# I2C_Switch.net
KiCad netlist of a schematic drawn in Altium Designer
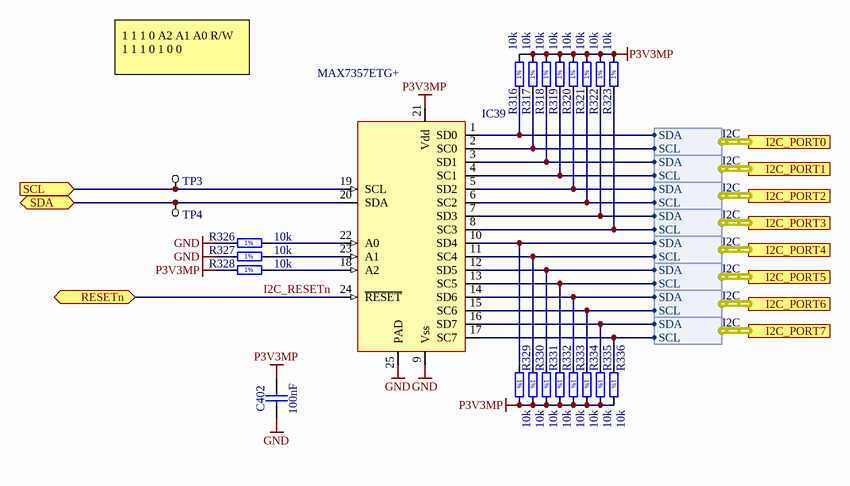
[diagram p0: I2C_Switch.SchDoc]

(export (version "E")
  (design (tool "Eeschema 10.0.6"))
  (components
    (comp (ref "C402")
      (value "100nF")
      (footprint "CAPC0603X33N")
      (description "Non-polarised capacitor")
      (fields
        (field (name "PART NUMBER") "CC0201_100NF_6.3V_10%_X5R")
        (field (name "VOLTAGE") "6.3V")
        (field (name "AUTHOR") "CERN DEM JLC")
      )
      (libsource (lib "Capacitors") (part "Capacitor - non polarized"))
    )
    (comp (ref "IC39")
      (value "MAX7357ETG+")
      (footprint "HVQFN24")
      (description "8-channel I2C-bus multiplexer with reset, INT and timeout")
      (libsource (lib "LIBRARY_SCH") (part "IIC_MUX_MAX7357ETG+"))
    )
    (comp (ref "R316")
      (value "10k")
      (footprint "RESC1005X40N")
      (description "Resistor - 1%")
      (fields
        (field (name "PART NUMBER") "R0402_10K_1%_0.0625W_100PPM")
        (field (name "POWER") "0.0625W")
        (field (name "AUTHOR") "CERN DEM JLC")
      )
      (libsource (lib "Resistors") (part "Resistor - 1%"))
    )
    (comp (ref "R317")
      (value "10k")
      (footprint "RESC1005X40N")
      (description "Resistor - 1%")
      (fields
        (field (name "PART NUMBER") "R0402_10K_1%_0.0625W_100PPM")
        (field (name "POWER") "0.0625W")
        (field (name "AUTHOR") "CERN DEM JLC")
      )
      (libsource (lib "Resistors") (part "Resistor - 1%"))
    )
    (comp (ref "R318")
      (value "10k")
      (footprint "RESC1005X40N")
      (description "Resistor - 1%")
      (fields
        (field (name "PART NUMBER") "R0402_10K_1%_0.0625W_100PPM")
        (field (name "POWER") "0.0625W")
        (field (name "AUTHOR") "CERN DEM JLC")
      )
      (libsource (lib "Resistors") (part "Resistor - 1%"))
    )
    (comp (ref "R319")
      (value "10k")
      (footprint "RESC1005X40N")
      (description "Resistor - 1%")
      (fields
        (field (name "PART NUMBER") "R0402_10K_1%_0.0625W_100PPM")
        (field (name "POWER") "0.0625W")
        (field (name "AUTHOR") "CERN DEM JLC")
      )
      (libsource (lib "Resistors") (part "Resistor - 1%"))
    )
    (comp (ref "R320")
      (value "10k")
      (footprint "RESC1005X40N")
      (description "Resistor - 1%")
      (fields
        (field (name "PART NUMBER") "R0402_10K_1%_0.0625W_100PPM")
        (field (name "POWER") "0.0625W")
        (field (name "AUTHOR") "CERN DEM JLC")
      )
      (libsource (lib "Resistors") (part "Resistor - 1%"))
    )
    (comp (ref "R321")
      (value "10k")
      (footprint "RESC1005X40N")
      (description "Resistor - 1%")
      (fields
        (field (name "PART NUMBER") "R0402_10K_1%_0.0625W_100PPM")
        (field (name "POWER") "0.0625W")
        (field (name "AUTHOR") "CERN DEM JLC")
      )
      (libsource (lib "Resistors") (part "Resistor - 1%"))
    )
    (comp (ref "R322")
      (value "10k")
      (footprint "RESC1005X40N")
      (description "Resistor - 1%")
      (fields
        (field (name "PART NUMBER") "R0402_10K_1%_0.0625W_100PPM")
        (field (name "POWER") "0.0625W")
        (field (name "AUTHOR") "CERN DEM JLC")
      )
      (libsource (lib "Resistors") (part "Resistor - 1%"))
    )
    (comp (ref "R323")
      (value "10k")
      (footprint "RESC1005X40N")
      (description "Resistor - 1%")
      (fields
        (field (name "PART NUMBER") "R0402_10K_1%_0.0625W_100PPM")
        (field (name "POWER") "0.0625W")
        (field (name "AUTHOR") "CERN DEM JLC")
      )
      (libsource (lib "Resistors") (part "Resistor - 1%"))
    )
    (comp (ref "R326")
      (value "10k")
      (footprint "RESC1005X40N")
      (description "Resistor - 1%")
      (fields
        (field (name "PART NUMBER") "R0402_10K_1%_0.0625W_100PPM")
        (field (name "POWER") "0.0625W")
        (field (name "AUTHOR") "CERN DEM JLC")
      )
      (libsource (lib "Resistors") (part "Resistor - 1%"))
    )
    (comp (ref "R327")
      (value "10k")
      (footprint "RESC1005X40N")
      (description "Resistor - 1%")
      (fields
        (field (name "PART NUMBER") "R0402_10K_1%_0.0625W_100PPM")
        (field (name "POWER") "0.0625W")
        (field (name "AUTHOR") "CERN DEM JLC")
      )
      (libsource (lib "Resistors") (part "Resistor - 1%"))
    )
    (comp (ref "R328")
      (value "10k")
      (footprint "RESC1005X40N")
      (description "Resistor - 1%")
      (fields
        (field (name "PART NUMBER") "R0402_10K_1%_0.0625W_100PPM")
        (field (name "POWER") "0.0625W")
        (field (name "AUTHOR") "CERN DEM JLC")
      )
      (libsource (lib "Resistors") (part "Resistor - 1%"))
    )
    (comp (ref "R329")
      (value "10k")
      (footprint "RESC1005X40N")
      (description "Resistor - 1%")
      (fields
        (field (name "PART NUMBER") "R0402_10K_1%_0.0625W_100PPM")
        (field (name "POWER") "0.0625W")
        (field (name "AUTHOR") "CERN DEM JLC")
      )
      (libsource (lib "Resistors") (part "Resistor - 1%"))
    )
    (comp (ref "R330")
      (value "10k")
      (footprint "RESC1005X40N")
      (description "Resistor - 1%")
      (fields
        (field (name "PART NUMBER") "R0402_10K_1%_0.0625W_100PPM")
        (field (name "POWER") "0.0625W")
        (field (name "AUTHOR") "CERN DEM JLC")
      )
      (libsource (lib "Resistors") (part "Resistor - 1%"))
    )
    (comp (ref "R331")
      (value "10k")
      (footprint "RESC1005X40N")
      (description "Resistor - 1%")
      (fields
        (field (name "PART NUMBER") "R0402_10K_1%_0.0625W_100PPM")
        (field (name "POWER") "0.0625W")
        (field (name "AUTHOR") "CERN DEM JLC")
      )
      (libsource (lib "Resistors") (part "Resistor - 1%"))
    )
    (comp (ref "R332")
      (value "10k")
      (footprint "RESC1005X40N")
      (description "Resistor - 1%")
      (fields
        (field (name "PART NUMBER") "R0402_10K_1%_0.0625W_100PPM")
        (field (name "POWER") "0.0625W")
        (field (name "AUTHOR") "CERN DEM JLC")
      )
      (libsource (lib "Resistors") (part "Resistor - 1%"))
    )
    (comp (ref "R333")
      (value "10k")
      (footprint "RESC1005X40N")
      (description "Resistor - 1%")
      (fields
        (field (name "PART NUMBER") "R0402_10K_1%_0.0625W_100PPM")
        (field (name "POWER") "0.0625W")
        (field (name "AUTHOR") "CERN DEM JLC")
      )
      (libsource (lib "Resistors") (part "Resistor - 1%"))
    )
    (comp (ref "R334")
      (value "10k")
      (footprint "RESC1005X40N")
      (description "Resistor - 1%")
      (fields
        (field (name "PART NUMBER") "R0402_10K_1%_0.0625W_100PPM")
        (field (name "POWER") "0.0625W")
        (field (name "AUTHOR") "CERN DEM JLC")
      )
      (libsource (lib "Resistors") (part "Resistor - 1%"))
    )
    (comp (ref "R335")
      (value "10k")
      (footprint "RESC1005X40N")
      (description "Resistor - 1%")
      (fields
        (field (name "PART NUMBER") "R0402_10K_1%_0.0625W_100PPM")
        (field (name "POWER") "0.0625W")
        (field (name "AUTHOR") "CERN DEM JLC")
      )
      (libsource (lib "Resistors") (part "Resistor - 1%"))
    )
    (comp (ref "R336")
      (value "10k")
      (footprint "RESC1005X40N")
      (description "Resistor - 1%")
      (fields
        (field (name "PART NUMBER") "R0402_10K_1%_0.0625W_100PPM")
        (field (name "POWER") "0.0625W")
        (field (name "AUTHOR") "CERN DEM JLC")
      )
      (libsource (lib "Resistors") (part "Resistor - 1%"))
    )
    (comp (ref "TP3")
      (value "TP")
      (footprint "TP")
      (description "Testpoint")
      (libsource (lib "LIBRARY_SCH") (part "TP"))
    )
    (comp (ref "TP4")
      (value "TP")
      (footprint "TP")
      (description "Testpoint")
      (libsource (lib "LIBRARY_SCH") (part "TP"))
    )
  )
  (nets
    (net (code "4") (name "/I2C_RESETn") (class "Default")
      (node (ref "IC39") (pin "24") (pinfunction "~{RESET}_24") (pintype "input"))
    )
    (net (code "5") (name "/SCL") (class "Default")
      (node (ref "IC39") (pin "19") (pinfunction "SCL_19") (pintype "input"))
      (node (ref "TP3") (pin "1") (pintype "passive"))
    )
    (net (code "6") (name "/SDA") (class "Default")
      (node (ref "IC39") (pin "20") (pinfunction "SDA_20") (pintype "bidirectional"))
      (node (ref "TP4") (pin "1") (pintype "passive"))
    )
    (net (code "8") (name "GND") (class "Default")
      (node (ref "C402") (pin "1") (pinfunction "1_1") (pintype "passive"))
      (node (ref "IC39") (pin "25") (pinfunction "PAD_25") (pintype "power_in"))
      (node (ref "IC39") (pin "9") (pinfunction "Vss_9") (pintype "power_in"))
      (node (ref "R326") (pin "1") (pinfunction "1_1") (pintype "passive"))
      (node (ref "R327") (pin "1") (pinfunction "1_1") (pintype "passive"))
    )
    (net (code "9") (name "Net-(IC39-A0)") (class "Default")
      (node (ref "IC39") (pin "22") (pinfunction "A0_22") (pintype "input"))
      (node (ref "R326") (pin "2") (pinfunction "2_2") (pintype "passive"))
    )
    (net (code "10") (name "Net-(IC39-A1)") (class "Default")
      (node (ref "IC39") (pin "23") (pinfunction "A1_23") (pintype "input"))
      (node (ref "R327") (pin "2") (pinfunction "2_2") (pintype "passive"))
    )
    (net (code "11") (name "Net-(IC39-A2)") (class "Default")
      (node (ref "IC39") (pin "18") (pinfunction "A2_18") (pintype "input"))
      (node (ref "R328") (pin "2") (pinfunction "2_2") (pintype "passive"))
    )
    (net (code "12") (name "Net-(IC39-SC0)") (class "Default")
      (node (ref "IC39") (pin "2") (pinfunction "SC0_2") (pintype "bidirectional"))
      (node (ref "R317") (pin "1") (pinfunction "1_1") (pintype "passive"))
    )
    (net (code "13") (name "Net-(IC39-SC1)") (class "Default")
      (node (ref "IC39") (pin "4") (pinfunction "SC1_4") (pintype "bidirectional"))
      (node (ref "R319") (pin "1") (pinfunction "1_1") (pintype "passive"))
    )
    (net (code "14") (name "Net-(IC39-SC2)") (class "Default")
      (node (ref "IC39") (pin "6") (pinfunction "SC2_6") (pintype "bidirectional"))
      (node (ref "R321") (pin "1") (pinfunction "1_1") (pintype "passive"))
    )
    (net (code "15") (name "Net-(IC39-SC3)") (class "Default")
      (node (ref "IC39") (pin "8") (pinfunction "SC3_8") (pintype "bidirectional"))
      (node (ref "R323") (pin "1") (pinfunction "1_1") (pintype "passive"))
    )
    (net (code "16") (name "Net-(IC39-SC4)") (class "Default")
      (node (ref "IC39") (pin "11") (pinfunction "SC4_11") (pintype "bidirectional"))
      (node (ref "R330") (pin "1") (pinfunction "1_1") (pintype "passive"))
    )
    (net (code "17") (name "Net-(IC39-SC5)") (class "Default")
      (node (ref "IC39") (pin "13") (pinfunction "SC5_13") (pintype "bidirectional"))
      (node (ref "R332") (pin "1") (pinfunction "1_1") (pintype "passive"))
    )
    (net (code "18") (name "Net-(IC39-SC6)") (class "Default")
      (node (ref "IC39") (pin "15") (pinfunction "SC6_15") (pintype "bidirectional"))
      (node (ref "R334") (pin "1") (pinfunction "1_1") (pintype "passive"))
    )
    (net (code "19") (name "Net-(IC39-SC7)") (class "Default")
      (node (ref "IC39") (pin "17") (pinfunction "SC7_17") (pintype "bidirectional"))
      (node (ref "R336") (pin "1") (pinfunction "1_1") (pintype "passive"))
    )
    (net (code "20") (name "Net-(IC39-SD0)") (class "Default")
      (node (ref "IC39") (pin "1") (pinfunction "SD0_1") (pintype "bidirectional"))
      (node (ref "R316") (pin "1") (pinfunction "1_1") (pintype "passive"))
    )
    (net (code "21") (name "Net-(IC39-SD1)") (class "Default")
      (node (ref "IC39") (pin "3") (pinfunction "SD1_3") (pintype "bidirectional"))
      (node (ref "R318") (pin "1") (pinfunction "1_1") (pintype "passive"))
    )
    (net (code "22") (name "Net-(IC39-SD2)") (class "Default")
      (node (ref "IC39") (pin "5") (pinfunction "SD2_5") (pintype "bidirectional"))
      (node (ref "R320") (pin "1") (pinfunction "1_1") (pintype "passive"))
    )
    (net (code "23") (name "Net-(IC39-SD3)") (class "Default")
      (node (ref "IC39") (pin "7") (pinfunction "SD3_7") (pintype "bidirectional"))
      (node (ref "R322") (pin "1") (pinfunction "1_1") (pintype "passive"))
    )
    (net (code "24") (name "Net-(IC39-SD4)") (class "Default")
      (node (ref "IC39") (pin "10") (pinfunction "SD4_10") (pintype "bidirectional"))
      (node (ref "R329") (pin "1") (pinfunction "1_1") (pintype "passive"))
    )
    (net (code "25") (name "Net-(IC39-SD5)") (class "Default")
      (node (ref "IC39") (pin "12") (pinfunction "SD5_12") (pintype "bidirectional"))
      (node (ref "R331") (pin "1") (pinfunction "1_1") (pintype "passive"))
    )
    (net (code "26") (name "Net-(IC39-SD6)") (class "Default")
      (node (ref "IC39") (pin "14") (pinfunction "SD6_14") (pintype "bidirectional"))
      (node (ref "R333") (pin "1") (pinfunction "1_1") (pintype "passive"))
    )
    (net (code "27") (name "Net-(IC39-SD7)") (class "Default")
      (node (ref "IC39") (pin "16") (pinfunction "SD7_16") (pintype "bidirectional"))
      (node (ref "R335") (pin "1") (pinfunction "1_1") (pintype "passive"))
    )
    (net (code "28") (name "P3V3MP") (class "Default")
      (node (ref "C402") (pin "2") (pinfunction "2_2") (pintype "passive"))
      (node (ref "IC39") (pin "21") (pinfunction "Vdd_21") (pintype "power_in"))
      (node (ref "R316") (pin "2") (pinfunction "2_2") (pintype "passive"))
      (node (ref "R317") (pin "2") (pinfunction "2_2") (pintype "passive"))
      (node (ref "R318") (pin "2") (pinfunction "2_2") (pintype "passive"))
      (node (ref "R319") (pin "2") (pinfunction "2_2") (pintype "passive"))
      (node (ref "R320") (pin "2") (pinfunction "2_2") (pintype "passive"))
      (node (ref "R321") (pin "2") (pinfunction "2_2") (pintype "passive"))
      (node (ref "R322") (pin "2") (pinfunction "2_2") (pintype "passive"))
      (node (ref "R323") (pin "2") (pinfunction "2_2") (pintype "passive"))
      (node (ref "R328") (pin "1") (pinfunction "1_1") (pintype "passive"))
      (node (ref "R329") (pin "2") (pinfunction "2_2") (pintype "passive"))
      (node (ref "R330") (pin "2") (pinfunction "2_2") (pintype "passive"))
      (node (ref "R331") (pin "2") (pinfunction "2_2") (pintype "passive"))
      (node (ref "R332") (pin "2") (pinfunction "2_2") (pintype "passive"))
      (node (ref "R333") (pin "2") (pinfunction "2_2") (pintype "passive"))
      (node (ref "R334") (pin "2") (pinfunction "2_2") (pintype "passive"))
      (node (ref "R335") (pin "2") (pinfunction "2_2") (pintype "passive"))
      (node (ref "R336") (pin "2") (pinfunction "2_2") (pintype "passive"))
    )
  )
)
